# schem.net
KiCad netlist of a schematic drawn in Altium Designer
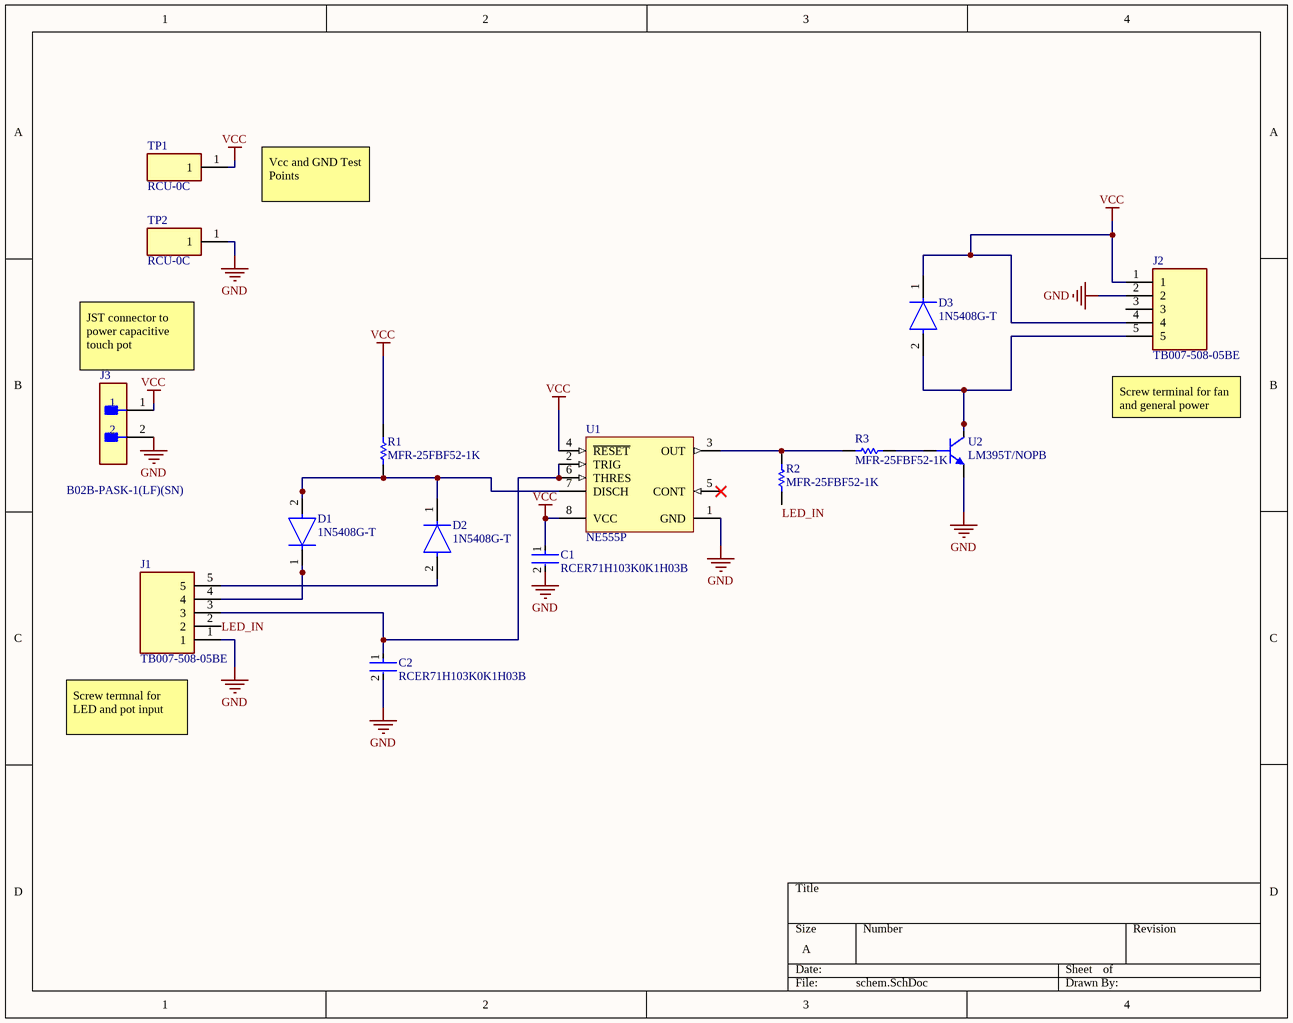
[diagram p0: schem.SchDoc]

(export (version "E")
  (design (tool "Eeschema 10.0.6"))
  (components
    (comp (ref "C1")
      (value "RCER71H103K0K1H03B")
      (footprint "FP-RCE0K1-MFG")
      (description "Cap Ceramic 10nF 50V X7R ±10% Radial 5mm +125°C Automotive Bulk")
      (fields (field (name "TOLERANCE") "10%"))
      (libsource (lib "Altium Content Vault") (part "b4654b650e69147ec39a6b967a45e02"))
    )
    (comp (ref "C2")
      (value "RCER71H103K0K1H03B")
      (footprint "FP-RCE0K1-MFG")
      (description "Cap Ceramic 10nF 50V X7R ±10% Radial 5mm +125°C Automotive Bulk")
      (fields (field (name "TOLERANCE") "10%"))
      (libsource (lib "Altium Content Vault") (part "b4654b650e69147ec39a6b967a45e02"))
    )
    (comp (ref "D1")
      (value "1N5408G-T")
      (footprint "FP-DO-201AD-MFG")
      (description "DIODE GEN PURP 1KV 3A DO201AD")
      (libsource (lib "Altium Content Vault") (part "d7152d700b627762746794eb795d46e"))
    )
    (comp (ref "D2")
      (value "1N5408G-T")
      (footprint "FP-DO-201AD-MFG")
      (description "DIODE GEN PURP 1KV 3A DO201AD")
      (libsource (lib "Altium Content Vault") (part "d7152d700b627762746794eb795d46e"))
    )
    (comp (ref "D3")
      (value "1N5408G-T")
      (footprint "FP-DO-201AD-MFG")
      (description "DIODE GEN PURP 1KV 3A DO201AD")
      (libsource (lib "Altium Content Vault") (part "d7152d700b627762746794eb795d46e"))
    )
    (comp (ref "J1")
      (value "TB007-508-05BE")
      (footprint "CUI_TB007-508-05BE")
      (libsource (lib "") (part "TB007-508-05BE_1"))
    )
    (comp (ref "J2")
      (value "TB007-508-05BE")
      (footprint "CUI_TB007-508-05BE")
      (libsource (lib "TB007-508-05BE") (part "TB007-508-05BE"))
    )
    (comp (ref "J3")
      (value "B02B-PASK-1(LF)(SN)")
      (footprint "FP-B02B-PASK-1_LF_SN-MFG")
      (description "CONN HEADER VERT 2POS 2MM")
      (libsource (lib "Altium Content Vault") (part "3bc925449376181038e59eaffc5286c"))
    )
    (comp (ref "R1")
      (value "MFR-25FBF52-1K")
      (footprint "RESA60-630X240")
      (description "Axial Resistor, 1 KOhm, +/- 1%, 250 mW, -55 to 155 degC, 2-Pin THD, RoHS, Bulk")
      (fields (field (name "TOLERANCE") "1%"))
      (libsource (lib "Altium Content Vault") (part "RES-2"))
    )
    (comp (ref "R2")
      (value "MFR-25FBF52-1K")
      (footprint "RESA60-630X240")
      (description "Axial Resistor, 1 KOhm, +/- 1%, 250 mW, -55 to 155 degC, 2-Pin THD, RoHS, Bulk")
      (fields (field (name "TOLERANCE") "1%"))
      (libsource (lib "Altium Content Vault") (part "RES-2"))
    )
    (comp (ref "R3")
      (value "MFR-25FBF52-1K")
      (footprint "RESA60-630X240")
      (description "Axial Resistor, 1 KOhm, +/- 1%, 250 mW, -55 to 155 degC, 2-Pin THD, RoHS, Bulk")
      (fields (field (name "TOLERANCE") "1%"))
      (libsource (lib "Altium Content Vault") (part "RES-2"))
    )
    (comp (ref "TP1")
      (value "RCU-0C")
      (footprint "TP+195X110")
      (description "Natural PC Test Point - - Plating Surface Mount Mounting Type")
      (fields (field (name "MF") "TE Connectivity AMP Connectors"))
      (libsource (lib "RCU-0C") (part "RCU-0C"))
    )
    (comp (ref "TP2")
      (value "RCU-0C")
      (footprint "TP+195X110")
      (description "Natural PC Test Point - - Plating Surface Mount Mounting Type")
      (fields (field (name "MF") "TE Connectivity AMP Connectors"))
      (libsource (lib "RCU-0C") (part "RCU-0C"))
    )
    (comp (ref "U1")
      (value "NE555P")
      (footprint "P0008A")
      (description "Precision Timer, 4.5 to 16 V, 0 to 70 degC, 8-Pin DIP, Pb-Free, Tube")
      (fields (field (name "MANUFACTURER") "TexasInstruments"))
      (libsource (lib "Altium Content Vault") (part "TI-NE555-P8"))
    )
    (comp (ref "U2")
      (value "LM395T/NOPB")
      (footprint "NDE0003A")
      (description "Ultra Reliable Power Transistor, 3-pin TO-220, Pb-Free")
      (fields (field (name "MANUFACTURER") "Texas Instruments"))
      (libsource (lib "Altium Content Vault") (part "DIS-Q-LM195-3B"))
    )
  )
  (nets
    (net (code "1") (name "/LED_IN") (class "Default")
      (node (ref "J1") (pin "2") (pinfunction "2_2") (pintype "passive"))
      (node (ref "R2") (pin "1") (pinfunction "1_1") (pintype "passive"))
    )
    (net (code "2") (name "GND") (class "Default")
      (node (ref "C1") (pin "2") (pinfunction "2_2") (pintype "passive"))
      (node (ref "C2") (pin "2") (pinfunction "2_2") (pintype "passive"))
      (node (ref "J1") (pin "1") (pinfunction "1_1") (pintype "passive"))
      (node (ref "J2") (pin "2") (pinfunction "2_2") (pintype "passive"))
      (node (ref "J3") (pin "2") (pinfunction "2_2") (pintype "passive"))
      (node (ref "TP2") (pin "1") (pinfunction "1_1") (pintype "passive"))
      (node (ref "U1") (pin "1") (pinfunction "GND_1") (pintype "power_in"))
      (node (ref "U2") (pin "2") (pinfunction "E_2") (pintype "passive"))
    )
    (net (code "3") (name "Net-(D1-A)") (class "Default")
      (node (ref "D1") (pin "2") (pinfunction "A_2") (pintype "passive"))
      (node (ref "D2") (pin "1") (pinfunction "C_1") (pintype "passive"))
      (node (ref "R1") (pin "1") (pinfunction "1_1") (pintype "passive"))
      (node (ref "U1") (pin "7") (pinfunction "DISCH_7") (pintype "open_collector"))
    )
    (net (code "4") (name "Net-(D1-C)") (class "Default")
      (node (ref "D1") (pin "1") (pinfunction "C_1") (pintype "passive"))
      (node (ref "J1") (pin "4") (pinfunction "4_4") (pintype "passive"))
    )
    (net (code "5") (name "Net-(D2-A)") (class "Default")
      (node (ref "D2") (pin "2") (pinfunction "A_2") (pintype "passive"))
      (node (ref "J1") (pin "5") (pinfunction "5_5") (pintype "passive"))
    )
    (net (code "6") (name "Net-(D3-A)") (class "Default")
      (node (ref "D3") (pin "2") (pinfunction "A_2") (pintype "passive"))
      (node (ref "J2") (pin "5") (pinfunction "5_5") (pintype "passive"))
      (node (ref "U2") (pin "3") (pinfunction "C_3") (pintype "passive"))
    )
    (net (code "7") (name "Net-(U1-OUT)") (class "Default")
      (node (ref "R2") (pin "2") (pinfunction "2_2") (pintype "passive"))
      (node (ref "R3") (pin "2") (pinfunction "2_2") (pintype "passive"))
      (node (ref "U1") (pin "3") (pinfunction "OUT_3") (pintype "output"))
    )
    (net (code "8") (name "Net-(U1-THRES)") (class "Default")
      (node (ref "C2") (pin "1") (pinfunction "1_1") (pintype "passive"))
      (node (ref "J1") (pin "3") (pinfunction "3_3") (pintype "passive"))
      (node (ref "U1") (pin "2") (pinfunction "TRIG_2") (pintype "input"))
      (node (ref "U1") (pin "6") (pinfunction "THRES_6") (pintype "input"))
    )
    (net (code "9") (name "Net-(U2-B)") (class "Default")
      (node (ref "R3") (pin "1") (pinfunction "1_1") (pintype "passive"))
      (node (ref "U2") (pin "1") (pinfunction "B_1") (pintype "passive"))
    )
    (net (code "10") (name "VCC") (class "Default")
      (node (ref "C1") (pin "1") (pinfunction "1_1") (pintype "passive"))
      (node (ref "D3") (pin "1") (pinfunction "C_1") (pintype "passive"))
      (node (ref "J2") (pin "1") (pinfunction "1_1") (pintype "passive"))
      (node (ref "J2") (pin "4") (pinfunction "4_4") (pintype "passive"))
      (node (ref "J3") (pin "1") (pinfunction "1_1") (pintype "passive"))
      (node (ref "R1") (pin "2") (pinfunction "2_2") (pintype "passive"))
      (node (ref "TP1") (pin "1") (pinfunction "1_1") (pintype "passive"))
      (node (ref "U1") (pin "4") (pinfunction "~{RESET}_4") (pintype "input"))
      (node (ref "U1") (pin "8") (pinfunction "VCC_8") (pintype "power_in"))
    )
    (net (code "11") (name "unconnected-(J2-Pad3)") (class "Default")
      (node (ref "J2") (pin "3") (pinfunction "3_3") (pintype "passive"))
    )
    (net (code "12") (name "unconnected-(U1-CONT-Pad5)") (class "Default")
      (node (ref "U1") (pin "5") (pinfunction "CONT_5") (pintype "input+no_connect"))
    )
  )
)
